# LPCB235_-_GIMBAL_BUFFER.net
KiCad netlist of a schematic drawn in Altium Designer
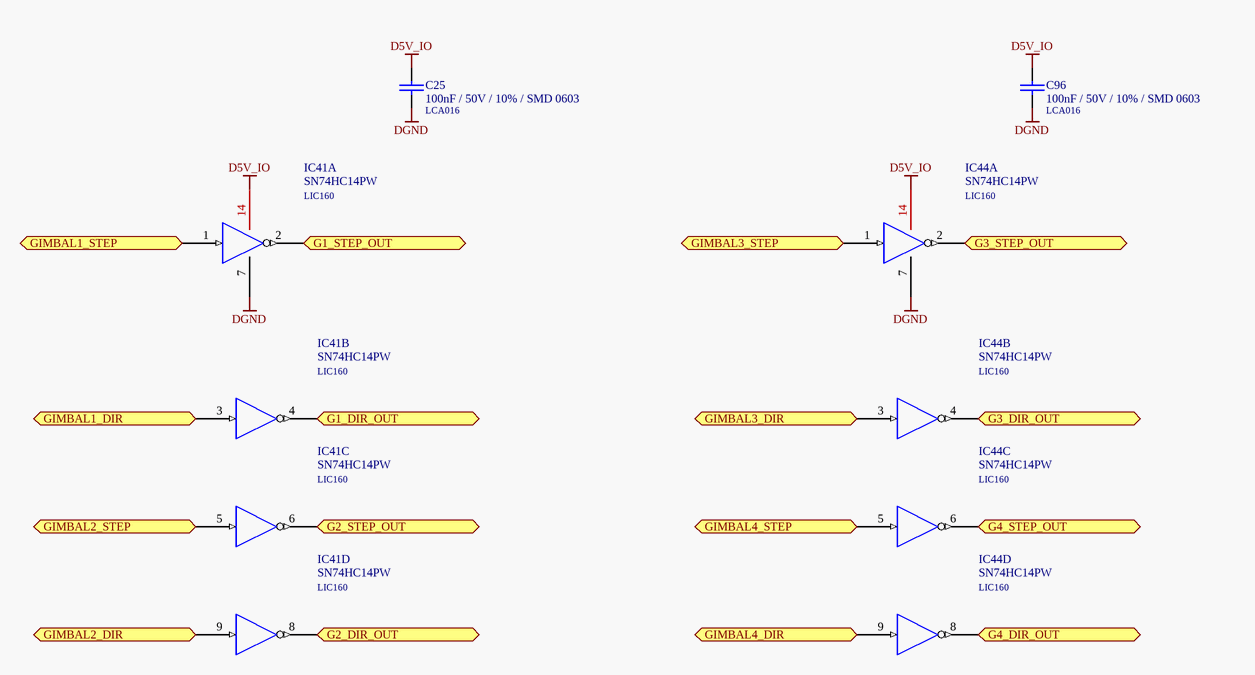
[diagram p0: LPCB235 - GIMBAL BUFFER.SchDoc]

(export (version "E")
  (design (tool "Eeschema 10.0.6"))
  (components
    (comp (ref "C25")
      (value "100nF / 50V / 10% / SMD 0603")
      (footprint "LFP011__CC1608-0603-IPC7351_B")
      (description "Capacitor, Ceramic Chip, 100nF (0.1uF), 50V, 5%, SMD 0603 [LCA016]")
      (fields (field (name "LDL_NUMBER") "LCA016"))
      (libsource (lib "LDL_Capacitors") (part "100nF / 50V / 10% / SMD 0603"))
    )
    (comp (ref "C96")
      (value "100nF / 50V / 10% / SMD 0603")
      (footprint "LFP011__CC1608-0603-IPC7351_B")
      (description "Capacitor, Ceramic Chip, 100nF (0.1uF), 50V, 5%, SMD 0603 [LCA016]")
      (fields (field (name "LDL_NUMBER") "LCA016"))
      (libsource (lib "LDL_Capacitors") (part "100nF / 50V / 10% / SMD 0603"))
    )
    (comp (ref "IC41")
      (value "SN74HC14PW")
      (footprint "PW014")
      (description "IC, Hex Inveter, Schmitt Trigger, SMD [LIC160]")
      (fields (field (name "LDL_NUMBER") "LIC160"))
      (libsource (lib "LDL_Semiconductors") (part "SN74HC14PW"))
    )
    (comp (ref "IC44")
      (value "SN74HC14PW")
      (footprint "PW014")
      (description "IC, Hex Inveter, Schmitt Trigger, SMD [LIC160]")
      (fields (field (name "LDL_NUMBER") "LIC160"))
      (libsource (lib "LDL_Semiconductors") (part "SN74HC14PW"))
    )
  )
  (nets
    (net (code "1") (name "/G1_DIR_OUT") (class "Default")
      (node (ref "IC41") (pin "4") (pinfunction "Y_4") (pintype "output"))
    )
    (net (code "2") (name "/G1_STEP_OUT") (class "Default")
      (node (ref "IC41") (pin "2") (pinfunction "Y_2") (pintype "output"))
    )
    (net (code "3") (name "/G2_DIR_OUT") (class "Default")
      (node (ref "IC41") (pin "8") (pinfunction "Y_8") (pintype "output"))
    )
    (net (code "4") (name "/G2_STEP_OUT") (class "Default")
      (node (ref "IC41") (pin "6") (pinfunction "Y_6") (pintype "output"))
    )
    (net (code "5") (name "/G3_DIR_OUT") (class "Default")
      (node (ref "IC44") (pin "4") (pinfunction "Y_4") (pintype "output"))
    )
    (net (code "6") (name "/G3_STEP_OUT") (class "Default")
      (node (ref "IC44") (pin "2") (pinfunction "Y_2") (pintype "output"))
    )
    (net (code "7") (name "/G4_DIR_OUT") (class "Default")
      (node (ref "IC44") (pin "8") (pinfunction "Y_8") (pintype "output"))
    )
    (net (code "8") (name "/G4_STEP_OUT") (class "Default")
      (node (ref "IC44") (pin "6") (pinfunction "Y_6") (pintype "output"))
    )
    (net (code "9") (name "/GIMBAL1_DIR") (class "Default")
      (node (ref "IC41") (pin "3") (pinfunction "A_3") (pintype "input"))
    )
    (net (code "10") (name "/GIMBAL1_STEP") (class "Default")
      (node (ref "IC41") (pin "1") (pinfunction "A_1") (pintype "input"))
    )
    (net (code "11") (name "/GIMBAL2_DIR") (class "Default")
      (node (ref "IC41") (pin "9") (pinfunction "A_9") (pintype "input"))
    )
    (net (code "12") (name "/GIMBAL2_STEP") (class "Default")
      (node (ref "IC41") (pin "5") (pinfunction "A_5") (pintype "input"))
    )
    (net (code "13") (name "/GIMBAL3_DIR") (class "Default")
      (node (ref "IC44") (pin "3") (pinfunction "A_3") (pintype "input"))
    )
    (net (code "14") (name "/GIMBAL3_STEP") (class "Default")
      (node (ref "IC44") (pin "1") (pinfunction "A_1") (pintype "input"))
    )
    (net (code "15") (name "/GIMBAL4_DIR") (class "Default")
      (node (ref "IC44") (pin "9") (pinfunction "A_9") (pintype "input"))
    )
    (net (code "16") (name "/GIMBAL4_STEP") (class "Default")
      (node (ref "IC44") (pin "5") (pinfunction "A_5") (pintype "input"))
    )
    (net (code "17") (name "D5V_IO") (class "Default")
      (node (ref "C25") (pin "1") (pintype "passive"))
      (node (ref "C96") (pin "1") (pintype "passive"))
      (node (ref "IC41") (pin "14") (pinfunction "VCC_14") (pintype "power_in"))
      (node (ref "IC44") (pin "14") (pinfunction "VCC_14") (pintype "power_in"))
    )
    (net (code "18") (name "DGND") (class "Default")
      (node (ref "C25") (pin "2") (pintype "passive"))
      (node (ref "C96") (pin "2") (pintype "passive"))
      (node (ref "IC41") (pin "7") (pinfunction "GND_7") (pintype "power_in"))
      (node (ref "IC44") (pin "7") (pinfunction "GND_7") (pintype "power_in"))
    )
  )
)
